# barBloom.net
KiCad netlist of a schematic drawn in EAGLE
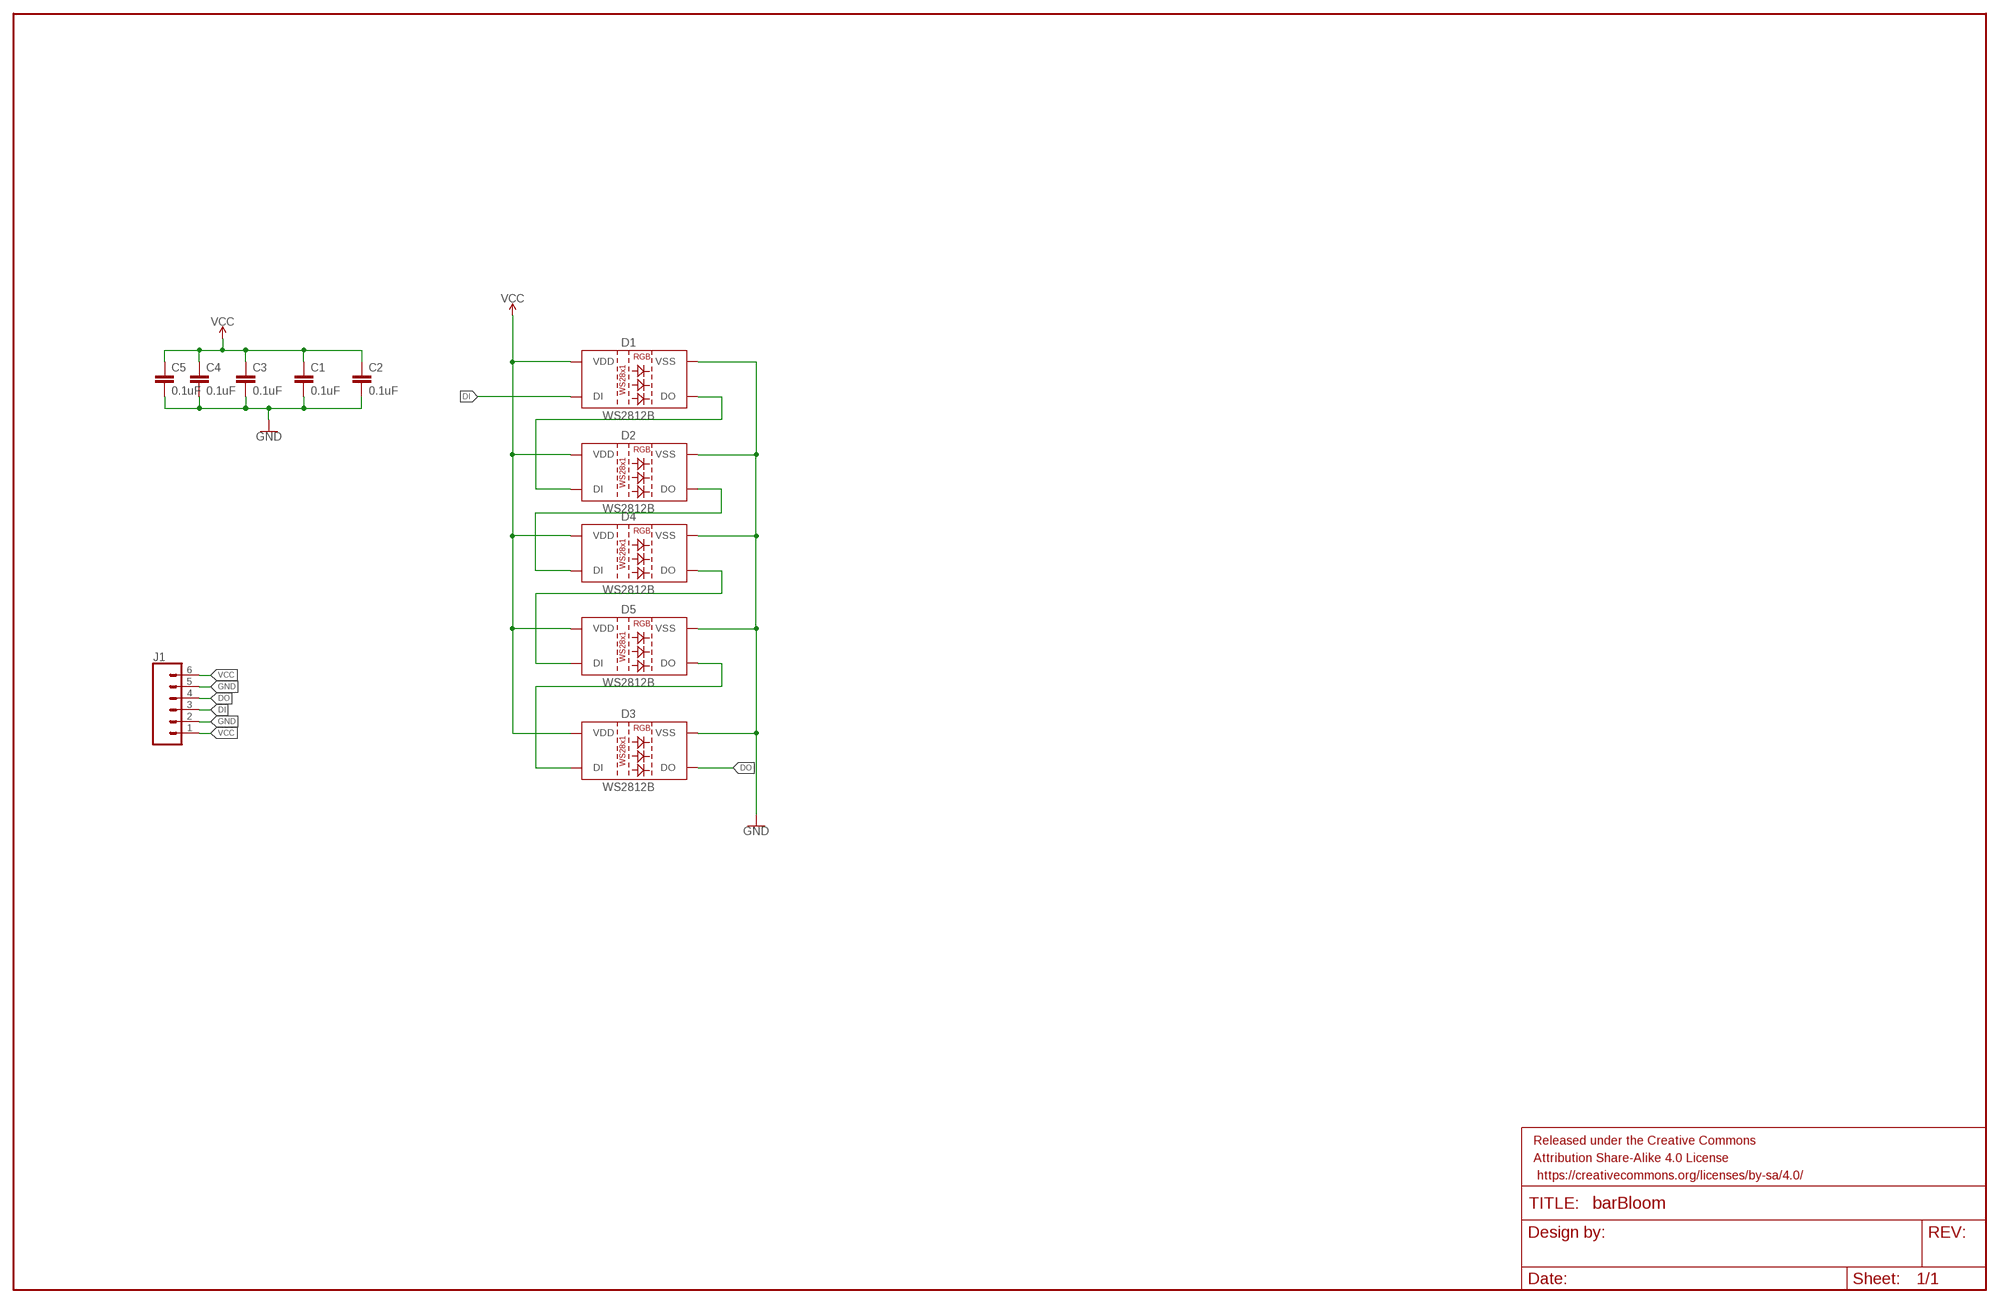
[diagram p0: schematic, sheet 1]

(export (version "E")
  (design (tool "Eeschema 10.0.6"))
  (components
    (comp (ref "C1")
      (value "0.1uF")
      (footprint "eagle-import:0603")
      (libsource (lib "eagle-import") (part "0.1UF-0603-25V-(+80/-20%)"))
    )
    (comp (ref "C2")
      (value "0.1uF")
      (footprint "eagle-import:0603")
      (libsource (lib "eagle-import") (part "0.1UF-0603-25V-(+80/-20%)"))
    )
    (comp (ref "C3")
      (value "0.1uF")
      (footprint "eagle-import:0603")
      (libsource (lib "eagle-import") (part "0.1UF-0603-25V-(+80/-20%)"))
    )
    (comp (ref "C4")
      (value "0.1uF")
      (footprint "eagle-import:0603")
      (libsource (lib "eagle-import") (part "0.1UF-0603-25V-(+80/-20%)"))
    )
    (comp (ref "C5")
      (value "0.1uF")
      (footprint "eagle-import:0603")
      (libsource (lib "eagle-import") (part "0.1UF-0603-25V-(+80/-20%)"))
    )
    (comp (ref "D1")
      (value "WS2812B")
      (footprint "eagle-import:WS2812B")
      (libsource (lib "eagle-import") (part "WS2812B"))
    )
    (comp (ref "D2")
      (value "WS2812B")
      (footprint "eagle-import:WS2812B")
      (libsource (lib "eagle-import") (part "WS2812B"))
    )
    (comp (ref "D3")
      (value "WS2812B")
      (footprint "eagle-import:WS2812B")
      (libsource (lib "eagle-import") (part "WS2812B"))
    )
    (comp (ref "D4")
      (value "WS2812B")
      (footprint "eagle-import:WS2812B")
      (libsource (lib "eagle-import") (part "WS2812B"))
    )
    (comp (ref "D5")
      (value "WS2812B")
      (footprint "eagle-import:WS2812B")
      (libsource (lib "eagle-import") (part "WS2812B"))
    )
    (comp (ref "FRAME1")
      (value "FRAME-LEDGER")
      (footprint "eagle-import:CREATIVE_COMMONS")
      (libsource (lib "eagle-import") (part "FRAME-LEDGER"))
    )
    (comp (ref "J1")
      (value "CONN_06SMD-STRAIGHT-ALT-FEMALE")
      (footprint "eagle-import:1X06_SMD_STRAIGHT_ALT")
      (libsource (lib "eagle-import") (part "CONN_06SMD-STRAIGHT-ALT-FEMALE"))
    )
  )
  (nets
    (net (code "1") (name "DI") (class "Default")
      (node (ref "D1") (pin "4") (pinfunction "DI_4") (pintype "bidirectional"))
      (node (ref "J1") (pin "3") (pinfunction "3_3") (pintype "passive"))
    )
    (net (code "2") (name "DO") (class "Default")
      (node (ref "D3") (pin "2") (pinfunction "DO_2") (pintype "bidirectional"))
      (node (ref "J1") (pin "4") (pinfunction "4_4") (pintype "passive"))
    )
    (net (code "3") (name "GND") (class "Default")
      (node (ref "C1") (pin "2") (pinfunction "2_2") (pintype "passive"))
      (node (ref "C2") (pin "2") (pinfunction "2_2") (pintype "passive"))
      (node (ref "C3") (pin "2") (pinfunction "2_2") (pintype "passive"))
      (node (ref "C4") (pin "2") (pinfunction "2_2") (pintype "passive"))
      (node (ref "C5") (pin "2") (pinfunction "2_2") (pintype "passive"))
      (node (ref "D1") (pin "3") (pinfunction "VSS_3") (pintype "bidirectional"))
      (node (ref "D2") (pin "3") (pinfunction "VSS_3") (pintype "bidirectional"))
      (node (ref "D3") (pin "3") (pinfunction "VSS_3") (pintype "bidirectional"))
      (node (ref "D4") (pin "3") (pinfunction "VSS_3") (pintype "bidirectional"))
      (node (ref "D5") (pin "3") (pinfunction "VSS_3") (pintype "bidirectional"))
      (node (ref "J1") (pin "2") (pinfunction "2_2") (pintype "passive"))
      (node (ref "J1") (pin "5") (pinfunction "5_5") (pintype "passive"))
    )
    (net (code "4") (name "Net-(D1-DO)") (class "Default")
      (node (ref "D1") (pin "2") (pinfunction "DO_2") (pintype "bidirectional"))
      (node (ref "D2") (pin "4") (pinfunction "DI_4") (pintype "bidirectional"))
    )
    (net (code "5") (name "Net-(D2-DO)") (class "Default")
      (node (ref "D2") (pin "2") (pinfunction "DO_2") (pintype "bidirectional"))
      (node (ref "D4") (pin "4") (pinfunction "DI_4") (pintype "bidirectional"))
    )
    (net (code "6") (name "Net-(D3-DI)") (class "Default")
      (node (ref "D3") (pin "4") (pinfunction "DI_4") (pintype "bidirectional"))
      (node (ref "D5") (pin "2") (pinfunction "DO_2") (pintype "bidirectional"))
    )
    (net (code "7") (name "Net-(D4-DO)") (class "Default")
      (node (ref "D4") (pin "2") (pinfunction "DO_2") (pintype "bidirectional"))
      (node (ref "D5") (pin "4") (pinfunction "DI_4") (pintype "bidirectional"))
    )
    (net (code "8") (name "VCC") (class "Default")
      (node (ref "C1") (pin "1") (pinfunction "1_1") (pintype "passive"))
      (node (ref "C2") (pin "1") (pinfunction "1_1") (pintype "passive"))
      (node (ref "C3") (pin "1") (pinfunction "1_1") (pintype "passive"))
      (node (ref "C4") (pin "1") (pinfunction "1_1") (pintype "passive"))
      (node (ref "C5") (pin "1") (pinfunction "1_1") (pintype "passive"))
      (node (ref "D1") (pin "1") (pinfunction "VDD_1") (pintype "bidirectional"))
      (node (ref "D2") (pin "1") (pinfunction "VDD_1") (pintype "bidirectional"))
      (node (ref "D3") (pin "1") (pinfunction "VDD_1") (pintype "bidirectional"))
      (node (ref "D4") (pin "1") (pinfunction "VDD_1") (pintype "bidirectional"))
      (node (ref "D5") (pin "1") (pinfunction "VDD_1") (pintype "bidirectional"))
      (node (ref "J1") (pin "1") (pinfunction "1_1") (pintype "passive"))
      (node (ref "J1") (pin "6") (pinfunction "6_6") (pintype "passive"))
    )
  )
)
